# v2.net
KiCad netlist of a schematic drawn in Altium Designer
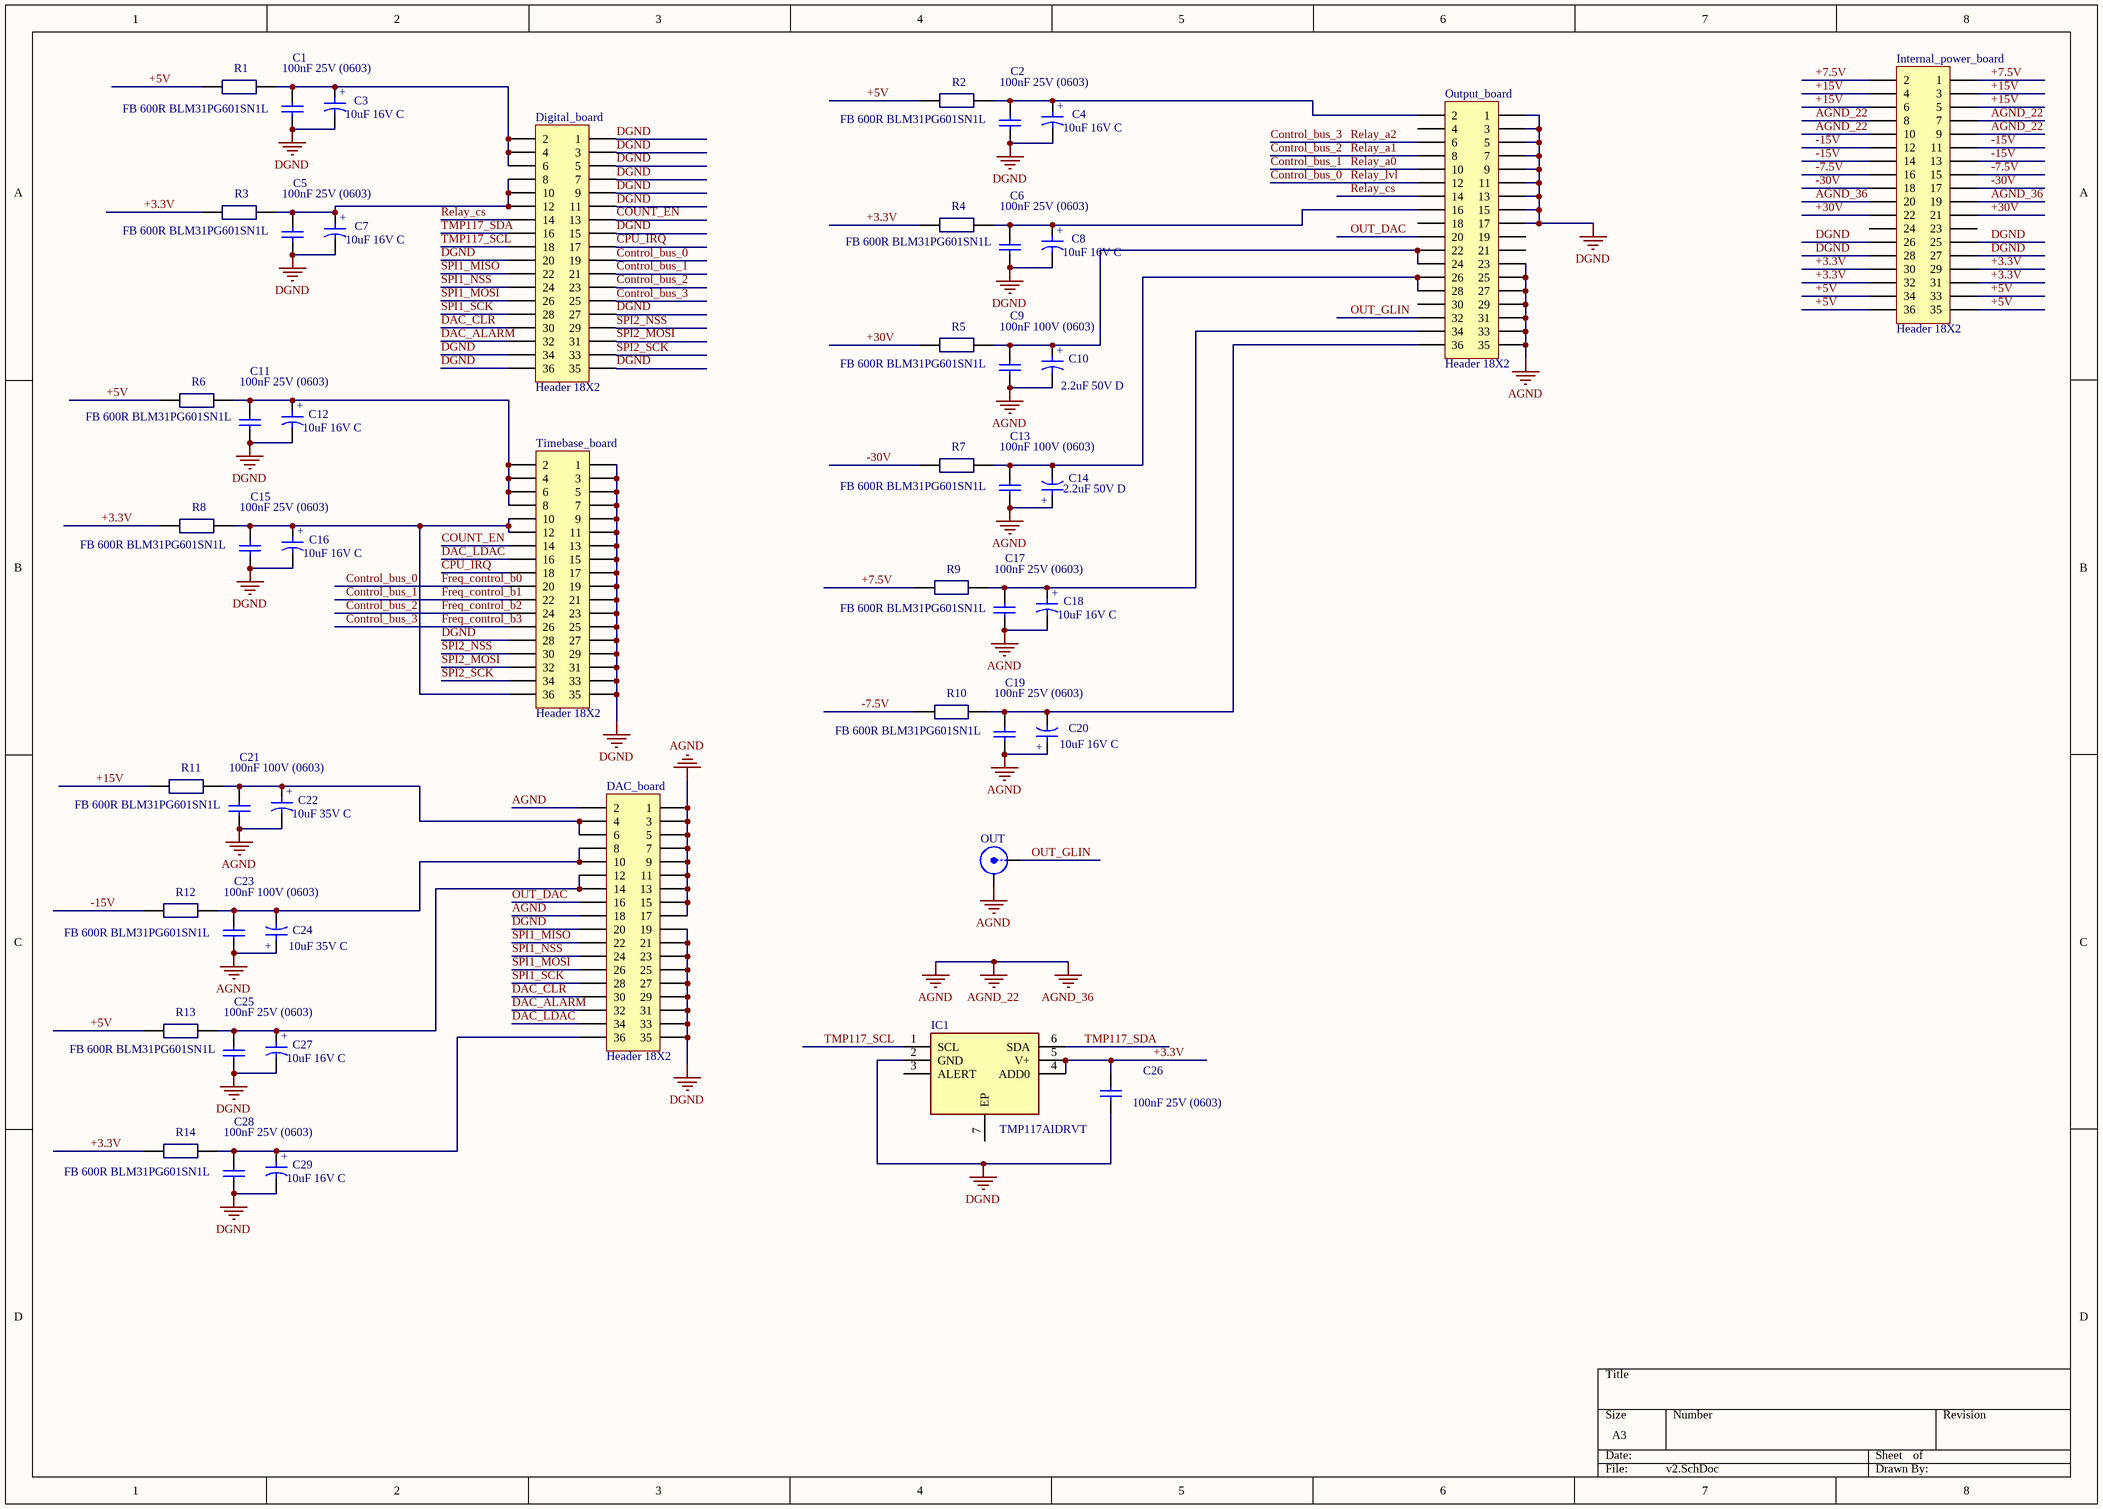
[diagram p0: v2.SchDoc]

(export (version "E")
  (design (tool "Eeschema 10.0.6"))
  (components
    (comp (ref "C1")
      (value "100nF 25V (0603)")
      (footprint "CAP 0603")
      (description "Capacitor (Semiconductor SIM Model)")
      (fields (field (name "PUBLISHER") "Altium Limited"))
      (libsource (lib "Miscellaneous Devices") (part "Cap Semi"))
    )
    (comp (ref "C2")
      (value "100nF 25V (0603)")
      (footprint "CAP 0603")
      (description "Capacitor (Semiconductor SIM Model)")
      (fields (field (name "PUBLISHER") "Altium Limited"))
      (libsource (lib "Miscellaneous Devices") (part "Cap Semi"))
    )
    (comp (ref "C3")
      (value "10uF 16V C")
      (footprint "CAPMP6032X280N")
      (description "Polarised capacitor")
      (fields
        (field (name "PART NUMBER") "CTE6032-28_10UF_25V_10%_LESR0500")
        (field (name "VOLTAGE") "25V")
        (field (name "AUTHOR") "CERN DEM JLC")
      )
      (libsource (lib "Capacitors") (part "Capacitor - polarized"))
    )
    (comp (ref "C4")
      (value "10uF 16V C")
      (footprint "CAPMP6032X280N")
      (description "Polarised capacitor")
      (fields
        (field (name "PART NUMBER") "CTE6032-28_10UF_25V_10%_LESR0500")
        (field (name "VOLTAGE") "25V")
        (field (name "AUTHOR") "CERN DEM JLC")
      )
      (libsource (lib "Capacitors") (part "Capacitor - polarized"))
    )
    (comp (ref "C5")
      (value "100nF 25V (0603)")
      (footprint "CAP 0603")
      (description "Capacitor (Semiconductor SIM Model)")
      (fields (field (name "PUBLISHER") "Altium Limited"))
      (libsource (lib "Miscellaneous Devices") (part "Cap Semi"))
    )
    (comp (ref "C6")
      (value "100nF 25V (0603)")
      (footprint "CAP 0603")
      (description "Capacitor (Semiconductor SIM Model)")
      (fields (field (name "PUBLISHER") "Altium Limited"))
      (libsource (lib "Miscellaneous Devices") (part "Cap Semi"))
    )
    (comp (ref "C7")
      (value "10uF 16V C")
      (footprint "CAPMP6032X280N")
      (description "Polarised capacitor")
      (fields
        (field (name "PART NUMBER") "CTE6032-28_10UF_25V_10%_LESR0500")
        (field (name "VOLTAGE") "25V")
        (field (name "AUTHOR") "CERN DEM JLC")
      )
      (libsource (lib "Capacitors") (part "Capacitor - polarized"))
    )
    (comp (ref "C8")
      (value "10uF 16V C")
      (footprint "CAPMP6032X280N")
      (description "Polarised capacitor")
      (fields
        (field (name "PART NUMBER") "CTE6032-28_10UF_25V_10%_LESR0500")
        (field (name "VOLTAGE") "25V")
        (field (name "AUTHOR") "CERN DEM JLC")
      )
      (libsource (lib "Capacitors") (part "Capacitor - polarized"))
    )
    (comp (ref "C9")
      (value "100nF 100V (0603)")
      (footprint "CAP 0603")
      (description "Capacitor (Semiconductor SIM Model)")
      (fields (field (name "PUBLISHER") "Altium Limited"))
      (libsource (lib "Miscellaneous Devices") (part "Cap Semi"))
    )
    (comp (ref "C10")
      (value "2.2uF 50V D")
      (footprint "CAPMP7343X310N")
      (description "Polarised capacitor")
      (fields
        (field (name "PART NUMBER") "CTE7343-31_22UF_35V_20%_LESR0400")
        (field (name "VOLTAGE") "35V")
        (field (name "AUTHOR") "CERN DEM MR")
      )
      (libsource (lib "Capacitors") (part "Capacitor - polarized"))
    )
    (comp (ref "C11")
      (value "100nF 25V (0603)")
      (footprint "CAP 0603")
      (description "Capacitor (Semiconductor SIM Model)")
      (fields (field (name "PUBLISHER") "Altium Limited"))
      (libsource (lib "Miscellaneous Devices") (part "Cap Semi"))
    )
    (comp (ref "C12")
      (value "10uF 16V C")
      (footprint "CAPMP6032X280N")
      (description "Polarised capacitor")
      (fields
        (field (name "PART NUMBER") "CTE6032-28_10UF_25V_10%_LESR0500")
        (field (name "VOLTAGE") "25V")
        (field (name "AUTHOR") "CERN DEM JLC")
      )
      (libsource (lib "Capacitors") (part "Capacitor - polarized"))
    )
    (comp (ref "C13")
      (value "100nF 100V (0603)")
      (footprint "CAP 0603")
      (description "Capacitor (Semiconductor SIM Model)")
      (fields (field (name "PUBLISHER") "Altium Limited"))
      (libsource (lib "Miscellaneous Devices") (part "Cap Semi"))
    )
    (comp (ref "C14")
      (value "2.2uF 50V D")
      (footprint "CAPMP7343X310N")
      (description "Polarised capacitor")
      (fields
        (field (name "PART NUMBER") "CTE7343-31_22UF_35V_20%_LESR0400")
        (field (name "VOLTAGE") "35V")
        (field (name "AUTHOR") "CERN DEM MR")
      )
      (libsource (lib "Capacitors") (part "Capacitor - polarized"))
    )
    (comp (ref "C15")
      (value "100nF 25V (0603)")
      (footprint "CAP 0603")
      (description "Capacitor (Semiconductor SIM Model)")
      (fields (field (name "PUBLISHER") "Altium Limited"))
      (libsource (lib "Miscellaneous Devices") (part "Cap Semi"))
    )
    (comp (ref "C16")
      (value "10uF 16V C")
      (footprint "CAPMP6032X280N")
      (description "Polarised capacitor")
      (fields
        (field (name "PART NUMBER") "CTE6032-28_10UF_25V_10%_LESR0500")
        (field (name "VOLTAGE") "25V")
        (field (name "AUTHOR") "CERN DEM JLC")
      )
      (libsource (lib "Capacitors") (part "Capacitor - polarized"))
    )
    (comp (ref "C17")
      (value "100nF 25V (0603)")
      (footprint "CAP 0603")
      (description "Capacitor (Semiconductor SIM Model)")
      (fields (field (name "PUBLISHER") "Altium Limited"))
      (libsource (lib "Miscellaneous Devices") (part "Cap Semi"))
    )
    (comp (ref "C18")
      (value "10uF 16V C")
      (footprint "CAPMP6032X280N")
      (description "Polarised capacitor")
      (fields
        (field (name "PART NUMBER") "CTE6032-28_10UF_25V_10%_LESR0500")
        (field (name "VOLTAGE") "25V")
        (field (name "AUTHOR") "CERN DEM JLC")
      )
      (libsource (lib "Capacitors") (part "Capacitor - polarized"))
    )
    (comp (ref "C19")
      (value "100nF 25V (0603)")
      (footprint "CAP 0603")
      (description "Capacitor (Semiconductor SIM Model)")
      (fields (field (name "PUBLISHER") "Altium Limited"))
      (libsource (lib "Miscellaneous Devices") (part "Cap Semi"))
    )
    (comp (ref "C20")
      (value "10uF 16V C")
      (footprint "CAPMP6032X280N")
      (description "Polarised capacitor")
      (fields
        (field (name "PART NUMBER") "CTE6032-28_10UF_25V_10%_LESR0500")
        (field (name "VOLTAGE") "25V")
        (field (name "AUTHOR") "CERN DEM JLC")
      )
      (libsource (lib "Capacitors") (part "Capacitor - polarized"))
    )
    (comp (ref "C21")
      (value "100nF 100V (0603)")
      (footprint "CAP 0603")
      (description "Capacitor (Semiconductor SIM Model)")
      (fields (field (name "PUBLISHER") "Altium Limited"))
      (libsource (lib "Miscellaneous Devices") (part "Cap Semi"))
    )
    (comp (ref "C22")
      (value "10uF 35V C")
      (footprint "CAPMP6032X280N")
      (description "Polarised capacitor")
      (fields
        (field (name "PART NUMBER") "CTE6032-28_10UF_25V_10%_LESR0500")
        (field (name "VOLTAGE") "25V")
        (field (name "AUTHOR") "CERN DEM JLC")
      )
      (libsource (lib "Capacitors") (part "Capacitor - polarized"))
    )
    (comp (ref "C23")
      (value "100nF 100V (0603)")
      (footprint "CAP 0603")
      (description "Capacitor (Semiconductor SIM Model)")
      (fields (field (name "PUBLISHER") "Altium Limited"))
      (libsource (lib "Miscellaneous Devices") (part "Cap Semi"))
    )
    (comp (ref "C24")
      (value "10uF 35V C")
      (footprint "CAPMP6032X280N")
      (description "Polarised capacitor")
      (fields
        (field (name "PART NUMBER") "CTE6032-28_10UF_25V_10%_LESR0500")
        (field (name "VOLTAGE") "25V")
        (field (name "AUTHOR") "CERN DEM JLC")
      )
      (libsource (lib "Capacitors") (part "Capacitor - polarized"))
    )
    (comp (ref "C25")
      (value "100nF 25V (0603)")
      (footprint "CAP 0603")
      (description "Capacitor (Semiconductor SIM Model)")
      (fields (field (name "PUBLISHER") "Altium Limited"))
      (libsource (lib "Miscellaneous Devices") (part "Cap Semi"))
    )
    (comp (ref "C26")
      (value "100nF 25V (0603)")
      (footprint "CAP 0603")
      (description "Capacitor (Semiconductor SIM Model)")
      (fields (field (name "PUBLISHER") "Altium Limited"))
      (libsource (lib "Miscellaneous Devices") (part "Cap Semi"))
    )
    (comp (ref "C27")
      (value "10uF 16V C")
      (footprint "CAPMP6032X280N")
      (description "Polarised capacitor")
      (fields
        (field (name "PART NUMBER") "CTE6032-28_10UF_25V_10%_LESR0500")
        (field (name "VOLTAGE") "25V")
        (field (name "AUTHOR") "CERN DEM JLC")
      )
      (libsource (lib "Capacitors") (part "Capacitor - polarized"))
    )
    (comp (ref "C28")
      (value "100nF 25V (0603)")
      (footprint "CAP 0603")
      (description "Capacitor (Semiconductor SIM Model)")
      (fields (field (name "PUBLISHER") "Altium Limited"))
      (libsource (lib "Miscellaneous Devices") (part "Cap Semi"))
    )
    (comp (ref "C29")
      (value "10uF 16V C")
      (footprint "CAPMP6032X280N")
      (description "Polarised capacitor")
      (fields
        (field (name "PART NUMBER") "CTE6032-28_10UF_25V_10%_LESR0500")
        (field (name "VOLTAGE") "25V")
        (field (name "AUTHOR") "CERN DEM JLC")
      )
      (libsource (lib "Capacitors") (part "Capacitor - polarized"))
    )
    (comp (ref "DAC_board")
      (value "Header 18X2")
      (footprint "HDR2X18")
      (description "Header, 18-Pin, Dual row")
      (fields (field (name "PUBLISHER") "Altium Limited"))
      (libsource (lib "Miscellaneous Connectors") (part "Header 18X2"))
    )
    (comp (ref "Digital_board")
      (value "Header 18X2")
      (footprint "HDR2X18")
      (description "Header, 18-Pin, Dual row")
      (fields (field (name "PUBLISHER") "Altium Limited"))
      (libsource (lib "Miscellaneous Connectors") (part "Header 18X2"))
    )
    (comp (ref "IC1")
      (value "TMP117AIDRVT")
      (footprint "SamacSys:SON65P200X200X80-7N-D")
      (description "Integrated Circuit")
      (fields (field (name "MOUSER PART NUMBER") "595-TMP117AIDRVT"))
      (libsource (lib "*") (part "TMP117AIDRVT"))
    )
    (comp (ref "Internal_power_board")
      (value "Header 18X2")
      (footprint "HDR2X18")
      (description "Header, 18-Pin, Dual row")
      (fields (field (name "PUBLISHER") "Altium Limited"))
      (libsource (lib "Miscellaneous Connectors") (part "Header 18X2"))
    )
    (comp (ref "OUT")
      (value "SMB")
      (footprint "SMB_V-RJ45")
      (description "SMB Straight Connector")
      (fields (field (name "PUBLISHER") "Altium Limited"))
      (libsource (lib "Miscellaneous Connectors") (part "SMB"))
    )
    (comp (ref "Output_board")
      (value "Header 18X2")
      (footprint "HDR2X18")
      (description "Header, 18-Pin, Dual row")
      (fields (field (name "PUBLISHER") "Altium Limited"))
      (libsource (lib "Miscellaneous Connectors") (part "Header 18X2"))
    )
    (comp (ref "R1")
      (value "FB 600R BLM31PG601SN1L")
      (footprint "C1206")
      (libsource (lib "Микрон-3") (part "Resistor 0805"))
    )
    (comp (ref "R2")
      (value "FB 600R BLM31PG601SN1L")
      (footprint "C1206")
      (libsource (lib "Микрон-3") (part "Resistor 0805"))
    )
    (comp (ref "R3")
      (value "FB 600R BLM31PG601SN1L")
      (footprint "C1206")
      (libsource (lib "Микрон-3") (part "Resistor 0805"))
    )
    (comp (ref "R4")
      (value "FB 600R BLM31PG601SN1L")
      (footprint "C1206")
      (libsource (lib "Микрон-3") (part "Resistor 0805"))
    )
    (comp (ref "R5")
      (value "FB 600R BLM31PG601SN1L")
      (footprint "C1206")
      (libsource (lib "Микрон-3") (part "Resistor 0805"))
    )
    (comp (ref "R6")
      (value "FB 600R BLM31PG601SN1L")
      (footprint "C1206")
      (libsource (lib "Микрон-3") (part "Resistor 0805"))
    )
    (comp (ref "R7")
      (value "FB 600R BLM31PG601SN1L")
      (footprint "C1206")
      (libsource (lib "Микрон-3") (part "Resistor 0805"))
    )
    (comp (ref "R8")
      (value "FB 600R BLM31PG601SN1L")
      (footprint "C1206")
      (libsource (lib "Микрон-3") (part "Resistor 0805"))
    )
    (comp (ref "R9")
      (value "FB 600R BLM31PG601SN1L")
      (footprint "C1206")
      (libsource (lib "Микрон-3") (part "Resistor 0805"))
    )
    (comp (ref "R10")
      (value "FB 600R BLM31PG601SN1L")
      (footprint "C1206")
      (libsource (lib "Микрон-3") (part "Resistor 0805"))
    )
    (comp (ref "R11")
      (value "FB 600R BLM31PG601SN1L")
      (footprint "C1206")
      (libsource (lib "Микрон-3") (part "Resistor 0805"))
    )
    (comp (ref "R12")
      (value "FB 600R BLM31PG601SN1L")
      (footprint "C1206")
      (libsource (lib "Микрон-3") (part "Resistor 0805"))
    )
    (comp (ref "R13")
      (value "FB 600R BLM31PG601SN1L")
      (footprint "C1206")
      (libsource (lib "Микрон-3") (part "Resistor 0805"))
    )
    (comp (ref "R14")
      (value "FB 600R BLM31PG601SN1L")
      (footprint "C1206")
      (libsource (lib "Микрон-3") (part "Resistor 0805"))
    )
    (comp (ref "Timebase_board")
      (value "Header 18X2")
      (footprint "HDR2X18")
      (description "Header, 18-Pin, Dual row")
      (fields (field (name "PUBLISHER") "Altium Limited"))
      (libsource (lib "Miscellaneous Connectors") (part "Header 18X2"))
    )
  )
  (nets
    (net (code "1") (name "/+3.3V") (class "Default")
      (node (ref "C26") (pin "1") (pinfunction "1_1") (pintype "passive"))
      (node (ref "IC1") (pin "4") (pinfunction "ADD0_4") (pintype "passive"))
      (node (ref "IC1") (pin "5") (pinfunction "V+_5") (pintype "passive"))
      (node (ref "Internal_power_board") (pin "29") (pinfunction "29_29") (pintype "passive"))
      (node (ref "Internal_power_board") (pin "30") (pinfunction "30_30") (pintype "passive"))
      (node (ref "Internal_power_board") (pin "31") (pinfunction "31_31") (pintype "passive"))
      (node (ref "Internal_power_board") (pin "32") (pinfunction "32_32") (pintype "passive"))
      (node (ref "R14") (pin "2") (pinfunction "2_2") (pintype "passive"))
      (node (ref "R3") (pin "2") (pinfunction "2_2") (pintype "passive"))
      (node (ref "R4") (pin "2") (pinfunction "2_2") (pintype "passive"))
      (node (ref "R8") (pin "2") (pinfunction "2_2") (pintype "passive"))
    )
    (net (code "2") (name "/+5V") (class "Default")
      (node (ref "Internal_power_board") (pin "33") (pinfunction "33_33") (pintype "passive"))
      (node (ref "Internal_power_board") (pin "34") (pinfunction "34_34") (pintype "passive"))
      (node (ref "Internal_power_board") (pin "35") (pinfunction "35_35") (pintype "passive"))
      (node (ref "Internal_power_board") (pin "36") (pinfunction "36_36") (pintype "passive"))
      (node (ref "R1") (pin "2") (pinfunction "2_2") (pintype "passive"))
      (node (ref "R13") (pin "2") (pinfunction "2_2") (pintype "passive"))
      (node (ref "R2") (pin "2") (pinfunction "2_2") (pintype "passive"))
      (node (ref "R6") (pin "2") (pinfunction "2_2") (pintype "passive"))
    )
    (net (code "3") (name "/+7.5V") (class "Default")
      (node (ref "Internal_power_board") (pin "1") (pinfunction "1_1") (pintype "passive"))
      (node (ref "Internal_power_board") (pin "2") (pinfunction "2_2") (pintype "passive"))
      (node (ref "R9") (pin "2") (pinfunction "2_2") (pintype "passive"))
    )
    (net (code "4") (name "/+15V") (class "Default")
      (node (ref "Internal_power_board") (pin "3") (pinfunction "3_3") (pintype "passive"))
      (node (ref "Internal_power_board") (pin "4") (pinfunction "4_4") (pintype "passive"))
      (node (ref "Internal_power_board") (pin "5") (pinfunction "5_5") (pintype "passive"))
      (node (ref "Internal_power_board") (pin "6") (pinfunction "6_6") (pintype "passive"))
      (node (ref "R11") (pin "2") (pinfunction "2_2") (pintype "passive"))
    )
    (net (code "5") (name "/+30V") (class "Default")
      (node (ref "Internal_power_board") (pin "21") (pinfunction "21_21") (pintype "passive"))
      (node (ref "Internal_power_board") (pin "22") (pinfunction "22_22") (pintype "passive"))
      (node (ref "R5") (pin "2") (pinfunction "2_2") (pintype "passive"))
    )
    (net (code "6") (name "/-7.5V") (class "Default")
      (node (ref "Internal_power_board") (pin "15") (pinfunction "15_15") (pintype "passive"))
      (node (ref "Internal_power_board") (pin "16") (pinfunction "16_16") (pintype "passive"))
      (node (ref "R10") (pin "2") (pinfunction "2_2") (pintype "passive"))
    )
    (net (code "7") (name "/-15V") (class "Default")
      (node (ref "Internal_power_board") (pin "11") (pinfunction "11_11") (pintype "passive"))
      (node (ref "Internal_power_board") (pin "12") (pinfunction "12_12") (pintype "passive"))
      (node (ref "Internal_power_board") (pin "13") (pinfunction "13_13") (pintype "passive"))
      (node (ref "Internal_power_board") (pin "14") (pinfunction "14_14") (pintype "passive"))
      (node (ref "R12") (pin "2") (pinfunction "2_2") (pintype "passive"))
    )
    (net (code "8") (name "/-30V") (class "Default")
      (node (ref "Internal_power_board") (pin "17") (pinfunction "17_17") (pintype "passive"))
      (node (ref "Internal_power_board") (pin "18") (pinfunction "18_18") (pintype "passive"))
      (node (ref "R7") (pin "2") (pinfunction "2_2") (pintype "passive"))
    )
    (net (code "9") (name "/COUNT_EN") (class "Default")
      (node (ref "Digital_board") (pin "13") (pinfunction "13_13") (pintype "passive"))
      (node (ref "Timebase_board") (pin "14") (pinfunction "14_14") (pintype "passive"))
    )
    (net (code "10") (name "/CPU_IRQ") (class "Default")
      (node (ref "Digital_board") (pin "17") (pinfunction "17_17") (pintype "passive"))
      (node (ref "Timebase_board") (pin "18") (pinfunction "18_18") (pintype "passive"))
    )
    (net (code "11") (name "/Control_bus_0") (class "Default")
      (node (ref "Digital_board") (pin "19") (pinfunction "19_19") (pintype "passive"))
      (node (ref "Output_board") (pin "12") (pinfunction "12_12") (pintype "passive"))
      (node (ref "Timebase_board") (pin "20") (pinfunction "20_20") (pintype "passive"))
    )
    (net (code "12") (name "/Control_bus_1") (class "Default")
      (node (ref "Digital_board") (pin "21") (pinfunction "21_21") (pintype "passive"))
      (node (ref "Output_board") (pin "10") (pinfunction "10_10") (pintype "passive"))
      (node (ref "Timebase_board") (pin "22") (pinfunction "22_22") (pintype "passive"))
    )
    (net (code "13") (name "/Control_bus_2") (class "Default")
      (node (ref "Digital_board") (pin "23") (pinfunction "23_23") (pintype "passive"))
      (node (ref "Output_board") (pin "8") (pinfunction "8_8") (pintype "passive"))
      (node (ref "Timebase_board") (pin "24") (pinfunction "24_24") (pintype "passive"))
    )
    (net (code "14") (name "/Control_bus_3") (class "Default")
      (node (ref "Digital_board") (pin "25") (pinfunction "25_25") (pintype "passive"))
      (node (ref "Output_board") (pin "6") (pinfunction "6_6") (pintype "passive"))
      (node (ref "Timebase_board") (pin "26") (pinfunction "26_26") (pintype "passive"))
    )
    (net (code "15") (name "/DAC_ALARM") (class "Default")
      (node (ref "DAC_board") (pin "32") (pinfunction "32_32") (pintype "passive"))
      (node (ref "Digital_board") (pin "32") (pinfunction "32_32") (pintype "passive"))
    )
    (net (code "16") (name "/DAC_CLR") (class "Default")
      (node (ref "DAC_board") (pin "30") (pinfunction "30_30") (pintype "passive"))
      (node (ref "Digital_board") (pin "30") (pinfunction "30_30") (pintype "passive"))
    )
    (net (code "17") (name "/DAC_LDAC") (class "Default")
      (node (ref "DAC_board") (pin "34") (pinfunction "34_34") (pintype "passive"))
      (node (ref "Timebase_board") (pin "16") (pinfunction "16_16") (pintype "passive"))
    )
    (net (code "18") (name "/OUT_DAC") (class "Default")
      (node (ref "DAC_board") (pin "16") (pinfunction "16_16") (pintype "passive"))
      (node (ref "Output_board") (pin "20") (pinfunction "20_20") (pintype "passive"))
    )
    (net (code "19") (name "/OUT_GLIN") (class "Default")
      (node (ref "OUT") (pin "1") (pinfunction "X_1") (pintype "passive"))
      (node (ref "Output_board") (pin "32") (pinfunction "32_32") (pintype "passive"))
    )
    (net (code "20") (name "/Relay_cs") (class "Default")
      (node (ref "Digital_board") (pin "14") (pinfunction "14_14") (pintype "passive"))
      (node (ref "Output_board") (pin "14") (pinfunction "14_14") (pintype "passive"))
    )
    (net (code "21") (name "/SPI1_MISO") (class "Default")
      (node (ref "DAC_board") (pin "22") (pinfunction "22_22") (pintype "passive"))
      (node (ref "Digital_board") (pin "22") (pinfunction "22_22") (pintype "passive"))
    )
    (net (code "22") (name "/SPI1_MOSI") (class "Default")
      (node (ref "DAC_board") (pin "26") (pinfunction "26_26") (pintype "passive"))
      (node (ref "Digital_board") (pin "26") (pinfunction "26_26") (pintype "passive"))
    )
    (net (code "23") (name "/SPI1_NSS") (class "Default")
      (node (ref "DAC_board") (pin "24") (pinfunction "24_24") (pintype "passive"))
      (node (ref "Digital_board") (pin "24") (pinfunction "24_24") (pintype "passive"))
    )
    (net (code "24") (name "/SPI1_SCK") (class "Default")
      (node (ref "DAC_board") (pin "28") (pinfunction "28_28") (pintype "passive"))
      (node (ref "Digital_board") (pin "28") (pinfunction "28_28") (pintype "passive"))
    )
    (net (code "25") (name "/SPI2_MOSI") (class "Default")
      (node (ref "Digital_board") (pin "31") (pinfunction "31_31") (pintype "passive"))
      (node (ref "Timebase_board") (pin "32") (pinfunction "32_32") (pintype "passive"))
    )
    (net (code "26") (name "/SPI2_NSS") (class "Default")
      (node (ref "Digital_board") (pin "29") (pinfunction "29_29") (pintype "passive"))
      (node (ref "Timebase_board") (pin "30") (pinfunction "30_30") (pintype "passive"))
    )
    (net (code "27") (name "/SPI2_SCK") (class "Default")
      (node (ref "Digital_board") (pin "33") (pinfunction "33_33") (pintype "passive"))
      (node (ref "Timebase_board") (pin "34") (pinfunction "34_34") (pintype "passive"))
    )
    (net (code "28") (name "/TMP117_SCL") (class "Default")
      (node (ref "Digital_board") (pin "18") (pinfunction "18_18") (pintype "passive"))
      (node (ref "IC1") (pin "1") (pinfunction "SCL_1") (pintype "passive"))
    )
    (net (code "29") (name "/TMP117_SDA") (class "Default")
      (node (ref "Digital_board") (pin "16") (pinfunction "16_16") (pintype "passive"))
      (node (ref "IC1") (pin "6") (pinfunction "SDA_6") (pintype "passive"))
    )
    (net (code "30") (name "AGND") (class "Default")
      (node (ref "C10") (pin "2") (pinfunction "2_2") (pintype "passive"))
      (node (ref "C13") (pin "2") (pinfunction "2_2") (pintype "passive"))
      (node (ref "C14") (pin "1") (pinfunction "1_1") (pintype "passive"))
      (node (ref "C17") (pin "2") (pinfunction "2_2") (pintype "passive"))
      (node (ref "C18") (pin "2") (pinfunction "2_2") (pintype "passive"))
      (node (ref "C19") (pin "2") (pinfunction "2_2") (pintype "passive"))
      (node (ref "C20") (pin "1") (pinfunction "1_1") (pintype "passive"))
      (node (ref "C21") (pin "2") (pinfunction "2_2") (pintype "passive"))
      (node (ref "C22") (pin "2") (pinfunction "2_2") (pintype "passive"))
      (node (ref "C23") (pin "2") (pinfunction "2_2") (pintype "passive"))
      (node (ref "C24") (pin "1") (pinfunction "1_1") (pintype "passive"))
      (node (ref "C9") (pin "2") (pinfunction "2_2") (pintype "passive"))
      (node (ref "DAC_board") (pin "1") (pinfunction "1_1") (pintype "passive"))
      (node (ref "DAC_board") (pin "11") (pinfunction "11_11") (pintype "passive"))
      (node (ref "DAC_board") (pin "13") (pinfunction "13_13") (pintype "passive"))
      (node (ref "DAC_board") (pin "15") (pinfunction "15_15") (pintype "passive"))
      (node (ref "DAC_board") (pin "17") (pinfunction "17_17") (pintype "passive"))
      (node (ref "DAC_board") (pin "18") (pinfunction "18_18") (pintype "passive"))
      (node (ref "DAC_board") (pin "2") (pinfunction "2_2") (pintype "passive"))
      (node (ref "DAC_board") (pin "3") (pinfunction "3_3") (pintype "passive"))
      (node (ref "DAC_board") (pin "5") (pinfunction "5_5") (pintype "passive"))
      (node (ref "DAC_board") (pin "7") (pinfunction "7_7") (pintype "passive"))
      (node (ref "DAC_board") (pin "9") (pinfunction "9_9") (pintype "passive"))
      (node (ref "Internal_power_board") (pin "10") (pinfunction "10_10") (pintype "passive"))
      (node (ref "Internal_power_board") (pin "19") (pinfunction "19_19") (pintype "passive"))
      (node (ref "Internal_power_board") (pin "20") (pinfunction "20_20") (pintype "passive"))
      (node (ref "Internal_power_board") (pin "7") (pinfunction "7_7") (pintype "passive"))
      (node (ref "Internal_power_board") (pin "8") (pinfunction "8_8") (pintype "passive"))
      (node (ref "Internal_power_board") (pin "9") (pinfunction "9_9") (pintype "passive"))
      (node (ref "OUT") (pin "2") (pinfunction "Y_2") (pintype "passive"))
      (node (ref "Output_board") (pin "23") (pinfunction "23_23") (pintype "passive"))
      (node (ref "Output_board") (pin "25") (pinfunction "25_25") (pintype "passive"))
      (node (ref "Output_board") (pin "27") (pinfunction "27_27") (pintype "passive"))
      (node (ref "Output_board") (pin "29") (pinfunction "29_29") (pintype "passive"))
      (node (ref "Output_board") (pin "31") (pinfunction "31_31") (pintype "passive"))
      (node (ref "Output_board") (pin "33") (pinfunction "33_33") (pintype "passive"))
      (node (ref "Output_board") (pin "35") (pinfunction "35_35") (pintype "passive"))
    )
    (net (code "31") (name "DGND") (class "Default")
      (node (ref "C1") (pin "2") (pinfunction "2_2") (pintype "passive"))
      (node (ref "C11") (pin "2") (pinfunction "2_2") (pintype "passive"))
      (node (ref "C12") (pin "2") (pinfunction "2_2") (pintype "passive"))
      (node (ref "C15") (pin "2") (pinfunction "2_2") (pintype "passive"))
      (node (ref "C16") (pin "2") (pinfunction "2_2") (pintype "passive"))
      (node (ref "C2") (pin "2") (pinfunction "2_2") (pintype "passive"))
      (node (ref "C25") (pin "2") (pinfunction "2_2") (pintype "passive"))
      (node (ref "C26") (pin "2") (pinfunction "2_2") (pintype "passive"))
      (node (ref "C27") (pin "2") (pinfunction "2_2") (pintype "passive"))
      (node (ref "C28") (pin "2") (pinfunction "2_2") (pintype "passive"))
      (node (ref "C29") (pin "2") (pinfunction "2_2") (pintype "passive"))
      (node (ref "C3") (pin "2") (pinfunction "2_2") (pintype "passive"))
      (node (ref "C4") (pin "2") (pinfunction "2_2") (pintype "passive"))
      (node (ref "C5") (pin "2") (pinfunction "2_2") (pintype "passive"))
      (node (ref "C6") (pin "2") (pinfunction "2_2") (pintype "passive"))
      (node (ref "C7") (pin "2") (pinfunction "2_2") (pintype "passive"))
      (node (ref "C8") (pin "2") (pinfunction "2_2") (pintype "passive"))
      (node (ref "DAC_board") (pin "19") (pinfunction "19_19") (pintype "passive"))
      (node (ref "DAC_board") (pin "20") (pinfunction "20_20") (pintype "passive"))
      (node (ref "DAC_board") (pin "21") (pinfunction "21_21") (pintype "passive"))
      (node (ref "DAC_board") (pin "23") (pinfunction "23_23") (pintype "passive"))
      (node (ref "DAC_board") (pin "25") (pinfunction "25_25") (pintype "passive"))
      (node (ref "DAC_board") (pin "27") (pinfunction "27_27") (pintype "passive"))
      (node (ref "DAC_board") (pin "29") (pinfunction "29_29") (pintype "passive"))
      (node (ref "DAC_board") (pin "31") (pinfunction "31_31") (pintype "passive"))
      (node (ref "DAC_board") (pin "33") (pinfunction "33_33") (pintype "passive"))
      (node (ref "DAC_board") (pin "35") (pinfunction "35_35") (pintype "passive"))
      (node (ref "Digital_board") (pin "1") (pinfunction "1_1") (pintype "passive"))
      (node (ref "Digital_board") (pin "11") (pinfunction "11_11") (pintype "passive"))
      (node (ref "Digital_board") (pin "15") (pinfunction "15_15") (pintype "passive"))
      (node (ref "Digital_board") (pin "20") (pinfunction "20_20") (pintype "passive"))
      (node (ref "Digital_board") (pin "27") (pinfunction "27_27") (pintype "passive"))
      (node (ref "Digital_board") (pin "3") (pinfunction "3_3") (pintype "passive"))
      (node (ref "Digital_board") (pin "34") (pinfunction "34_34") (pintype "passive"))
      (node (ref "Digital_board") (pin "35") (pinfunction "35_35") (pintype "passive"))
      (node (ref "Digital_board") (pin "36") (pinfunction "36_36") (pintype "passive"))
      (node (ref "Digital_board") (pin "5") (pinfunction "5_5") (pintype "passive"))
      (node (ref "Digital_board") (pin "7") (pinfunction "7_7") (pintype "passive"))
      (node (ref "Digital_board") (pin "9") (pinfunction "9_9") (pintype "passive"))
      (node (ref "IC1") (pin "2") (pinfunction "GND_2") (pintype "passive"))
      (node (ref "Internal_power_board") (pin "25") (pinfunction "25_25") (pintype "passive"))
      (node (ref "Internal_power_board") (pin "26") (pinfunction "26_26") (pintype "passive"))
      (node (ref "Internal_power_board") (pin "27") (pinfunction "27_27") (pintype "passive"))
      (node (ref "Internal_power_board") (pin "28") (pinfunction "28_28") (pintype "passive"))
      (node (ref "Output_board") (pin "1") (pinfunction "1_1") (pintype "passive"))
      (node (ref "Output_board") (pin "11") (pinfunction "11_11") (pintype "passive"))
      (node (ref "Output_board") (pin "13") (pinfunction "13_13") (pintype "passive"))
      (node (ref "Output_board") (pin "15") (pinfunction "15_15") (pintype "passive"))
      (node (ref "Output_board") (pin "17") (pinfunction "17_17") (pintype "passive"))
      (node (ref "Output_board") (pin "3") (pinfunction "3_3") (pintype "passive"))
      (node (ref "Output_board") (pin "5") (pinfunction "5_5") (pintype "passive"))
      (node (ref "Output_board") (pin "7") (pinfunction "7_7") (pintype "passive"))
      (node (ref "Output_board") (pin "9") (pinfunction "9_9") (pintype "passive"))
      (node (ref "Timebase_board") (pin "1") (pinfunction "1_1") (pintype "passive"))
      (node (ref "Timebase_board") (pin "11") (pinfunction "11_11") (pintype "passive"))
      (node (ref "Timebase_board") (pin "13") (pinfunction "13_13") (pintype "passive"))
      (node (ref "Timebase_board") (pin "15") (pinfunction "15_15") (pintype "passive"))
      (node (ref "Timebase_board") (pin "17") (pinfunction "17_17") (pintype "passive"))
      (node (ref "Timebase_board") (pin "19") (pinfunction "19_19") (pintype "passive"))
      (node (ref "Timebase_board") (pin "21") (pinfunction "21_21") (pintype "passive"))
      (node (ref "Timebase_board") (pin "23") (pinfunction "23_23") (pintype "passive"))
      (node (ref "Timebase_board") (pin "25") (pinfunction "25_25") (pintype "passive"))
      (node (ref "Timebase_board") (pin "27") (pinfunction "27_27") (pintype "passive"))
      (node (ref "Timebase_board") (pin "28") (pinfunction "28_28") (pintype "passive"))
      (node (ref "Timebase_board") (pin "29") (pinfunction "29_29") (pintype "passive"))
      (node (ref "Timebase_board") (pin "3") (pinfunction "3_3") (pintype "passive"))
      (node (ref "Timebase_board") (pin "31") (pinfunction "31_31") (pintype "passive"))
      (node (ref "Timebase_board") (pin "33") (pinfunction "33_33") (pintype "passive"))
      (node (ref "Timebase_board") (pin "35") (pinfunction "35_35") (pintype "passive"))
      (node (ref "Timebase_board") (pin "5") (pinfunction "5_5") (pintype "passive"))
      (node (ref "Timebase_board") (pin "7") (pinfunction "7_7") (pintype "passive"))
      (node (ref "Timebase_board") (pin "9") (pinfunction "9_9") (pintype "passive"))
    )
    (net (code "32") (name "Net-(R1-A)") (class "Default")
      (node (ref "C1") (pin "1") (pinfunction "1_1") (pintype "passive"))
      (node (ref "C3") (pin "1") (pinfunction "1_1") (pintype "passive"))
      (node (ref "Digital_board") (pin "2") (pinfunction "2_2") (pintype "passive"))
      (node (ref "Digital_board") (pin "4") (pinfunction "4_4") (pintype "passive"))
      (node (ref "Digital_board") (pin "6") (pinfunction "6_6") (pintype "passive"))
      (node (ref "R1") (pin "1") (pinfunction "A_1") (pintype "passive"))
    )
    (net (code "33") (name "Net-(R2-A)") (class "Default")
      (node (ref "C2") (pin "1") (pinfunction "1_1") (pintype "passive"))
      (node (ref "C4") (pin "1") (pinfunction "1_1") (pintype "passive"))
      (node (ref "Output_board") (pin "2") (pinfunction "2_2") (pintype "passive"))
      (node (ref "R2") (pin "1") (pinfunction "A_1") (pintype "passive"))
    )
    (net (code "34") (name "Net-(R3-A)") (class "Default")
      (node (ref "C5") (pin "1") (pinfunction "1_1") (pintype "passive"))
      (node (ref "C7") (pin "1") (pinfunction "1_1") (pintype "passive"))
      (node (ref "Digital_board") (pin "10") (pinfunction "10_10") (pintype "passive"))
      (node (ref "Digital_board") (pin "12") (pinfunction "12_12") (pintype "passive"))
      (node (ref "Digital_board") (pin "8") (pinfunction "8_8") (pintype "passive"))
      (node (ref "R3") (pin "1") (pinfunction "A_1") (pintype "passive"))
    )
    (net (code "35") (name "Net-(R4-A)") (class "Default")
      (node (ref "C6") (pin "1") (pinfunction "1_1") (pintype "passive"))
      (node (ref "C8") (pin "1") (pinfunction "1_1") (pintype "passive"))
      (node (ref "Output_board") (pin "16") (pinfunction "16_16") (pintype "passive"))
      (node (ref "R4") (pin "1") (pinfunction "A_1") (pintype "passive"))
    )
    (net (code "36") (name "Net-(R5-A)") (class "Default")
      (node (ref "C10") (pin "1") (pinfunction "1_1") (pintype "passive"))
      (node (ref "C9") (pin "1") (pinfunction "1_1") (pintype "passive"))
      (node (ref "Output_board") (pin "22") (pinfunction "22_22") (pintype "passive"))
      (node (ref "Output_board") (pin "24") (pinfunction "24_24") (pintype "passive"))
      (node (ref "R5") (pin "1") (pinfunction "A_1") (pintype "passive"))
    )
    (net (code "37") (name "Net-(R6-A)") (class "Default")
      (node (ref "C11") (pin "1") (pinfunction "1_1") (pintype "passive"))
      (node (ref "C12") (pin "1") (pinfunction "1_1") (pintype "passive"))
      (node (ref "R6") (pin "1") (pinfunction "A_1") (pintype "passive"))
      (node (ref "Timebase_board") (pin "2") (pinfunction "2_2") (pintype "passive"))
      (node (ref "Timebase_board") (pin "4") (pinfunction "4_4") (pintype "passive"))
      (node (ref "Timebase_board") (pin "6") (pinfunction "6_6") (pintype "passive"))
      (node (ref "Timebase_board") (pin "8") (pinfunction "8_8") (pintype "passive"))
    )
    (net (code "38") (name "Net-(R7-A)") (class "Default")
      (node (ref "C13") (pin "1") (pinfunction "1_1") (pintype "passive"))
      (node (ref "C14") (pin "2") (pinfunction "2_2") (pintype "passive"))
      (node (ref "Output_board") (pin "26") (pinfunction "26_26") (pintype "passive"))
      (node (ref "Output_board") (pin "28") (pinfunction "28_28") (pintype "passive"))
      (node (ref "R7") (pin "1") (pinfunction "A_1") (pintype "passive"))
    )
    (net (code "39") (name "Net-(R8-A)") (class "Default")
      (node (ref "C15") (pin "1") (pinfunction "1_1") (pintype "passive"))
      (node (ref "C16") (pin "1") (pinfunction "1_1") (pintype "passive"))
      (node (ref "R8") (pin "1") (pinfunction "A_1") (pintype "passive"))
      (node (ref "Timebase_board") (pin "10") (pinfunction "10_10") (pintype "passive"))
      (node (ref "Timebase_board") (pin "12") (pinfunction "12_12") (pintype "passive"))
      (node (ref "Timebase_board") (pin "36") (pinfunction "36_36") (pintype "passive"))
    )
    (net (code "40") (name "Net-(R9-A)") (class "Default")
      (node (ref "C17") (pin "1") (pinfunction "1_1") (pintype "passive"))
      (node (ref "C18") (pin "1") (pinfunction "1_1") (pintype "passive"))
      (node (ref "Output_board") (pin "34") (pinfunction "34_34") (pintype "passive"))
      (node (ref "R9") (pin "1") (pinfunction "A_1") (pintype "passive"))
    )
    (net (code "41") (name "Net-(R10-A)") (class "Default")
      (node (ref "C19") (pin "1") (pinfunction "1_1") (pintype "passive"))
      (node (ref "C20") (pin "2") (pinfunction "2_2") (pintype "passive"))
      (node (ref "Output_board") (pin "36") (pinfunction "36_36") (pintype "passive"))
      (node (ref "R10") (pin "1") (pinfunction "A_1") (pintype "passive"))
    )
    (net (code "42") (name "Net-(R11-A)") (class "Default")
      (node (ref "C21") (pin "1") (pinfunction "1_1") (pintype "passive"))
      (node (ref "C22") (pin "1") (pinfunction "1_1") (pintype "passive"))
      (node (ref "DAC_board") (pin "4") (pinfunction "4_4") (pintype "passive"))
      (node (ref "DAC_board") (pin "6") (pinfunction "6_6") (pintype "passive"))
      (node (ref "R11") (pin "1") (pinfunction "A_1") (pintype "passive"))
    )
    (net (code "43") (name "Net-(R12-A)") (class "Default")
      (node (ref "C23") (pin "1") (pinfunction "1_1") (pintype "passive"))
      (node (ref "C24") (pin "2") (pinfunction "2_2") (pintype "passive"))
      (node (ref "DAC_board") (pin "10") (pinfunction "10_10") (pintype "passive"))
      (node (ref "DAC_board") (pin "8") (pinfunction "8_8") (pintype "passive"))
      (node (ref "R12") (pin "1") (pinfunction "A_1") (pintype "passive"))
    )
    (net (code "44") (name "Net-(R13-A)") (class "Default")
      (node (ref "C25") (pin "1") (pinfunction "1_1") (pintype "passive"))
      (node (ref "C27") (pin "1") (pinfunction "1_1") (pintype "passive"))
      (node (ref "DAC_board") (pin "12") (pinfunction "12_12") (pintype "passive"))
      (node (ref "DAC_board") (pin "14") (pinfunction "14_14") (pintype "passive"))
      (node (ref "R13") (pin "1") (pinfunction "A_1") (pintype "passive"))
    )
    (net (code "45") (name "Net-(R14-A)") (class "Default")
      (node (ref "C28") (pin "1") (pinfunction "1_1") (pintype "passive"))
      (node (ref "C29") (pin "1") (pinfunction "1_1") (pintype "passive"))
      (node (ref "DAC_board") (pin "36") (pinfunction "36_36") (pintype "passive"))
      (node (ref "R14") (pin "1") (pinfunction "A_1") (pintype "passive"))
    )
    (net (code "46") (name "unconnected-(IC1-ALERT-Pad3)") (class "Default")
      (node (ref "IC1") (pin "3") (pinfunction "ALERT_3") (pintype "passive"))
    )
    (net (code "47") (name "unconnected-(IC1-EP-Pad7)") (class "Default")
      (node (ref "IC1") (pin "7") (pinfunction "EP_7") (pintype "passive"))
    )
    (net (code "48") (name "unconnected-(Internal_power_board-Pad23)") (class "Default")
      (node (ref "Internal_power_board") (pin "23") (pinfunction "23_23") (pintype "passive"))
    )
    (net (code "49") (name "unconnected-(Internal_power_board-Pad24)") (class "Default")
      (node (ref "Internal_power_board") (pin "24") (pinfunction "24_24") (pintype "passive"))
    )
    (net (code "50") (name "unconnected-(Output_board-Pad4)") (class "Default")
      (node (ref "Output_board") (pin "4") (pinfunction "4_4") (pintype "passive"))
    )
    (net (code "51") (name "unconnected-(Output_board-Pad18)") (class "Default")
      (node (ref "Output_board") (pin "18") (pinfunction "18_18") (pintype "passive"))
    )
    (net (code "52") (name "unconnected-(Output_board-Pad19)") (class "Default")
      (node (ref "Output_board") (pin "19") (pinfunction "19_19") (pintype "passive"))
    )
    (net (code "53") (name "unconnected-(Output_board-Pad21)") (class "Default")
      (node (ref "Output_board") (pin "21") (pinfunction "21_21") (pintype "passive"))
    )
    (net (code "54") (name "unconnected-(Output_board-Pad30)") (class "Default")
      (node (ref "Output_board") (pin "30") (pinfunction "30_30") (pintype "passive"))
    )
  )
)
